# SCH_MedicalIOT_2023-03-18.net
KiCad netlist of a schematic drawn in EasyEDA
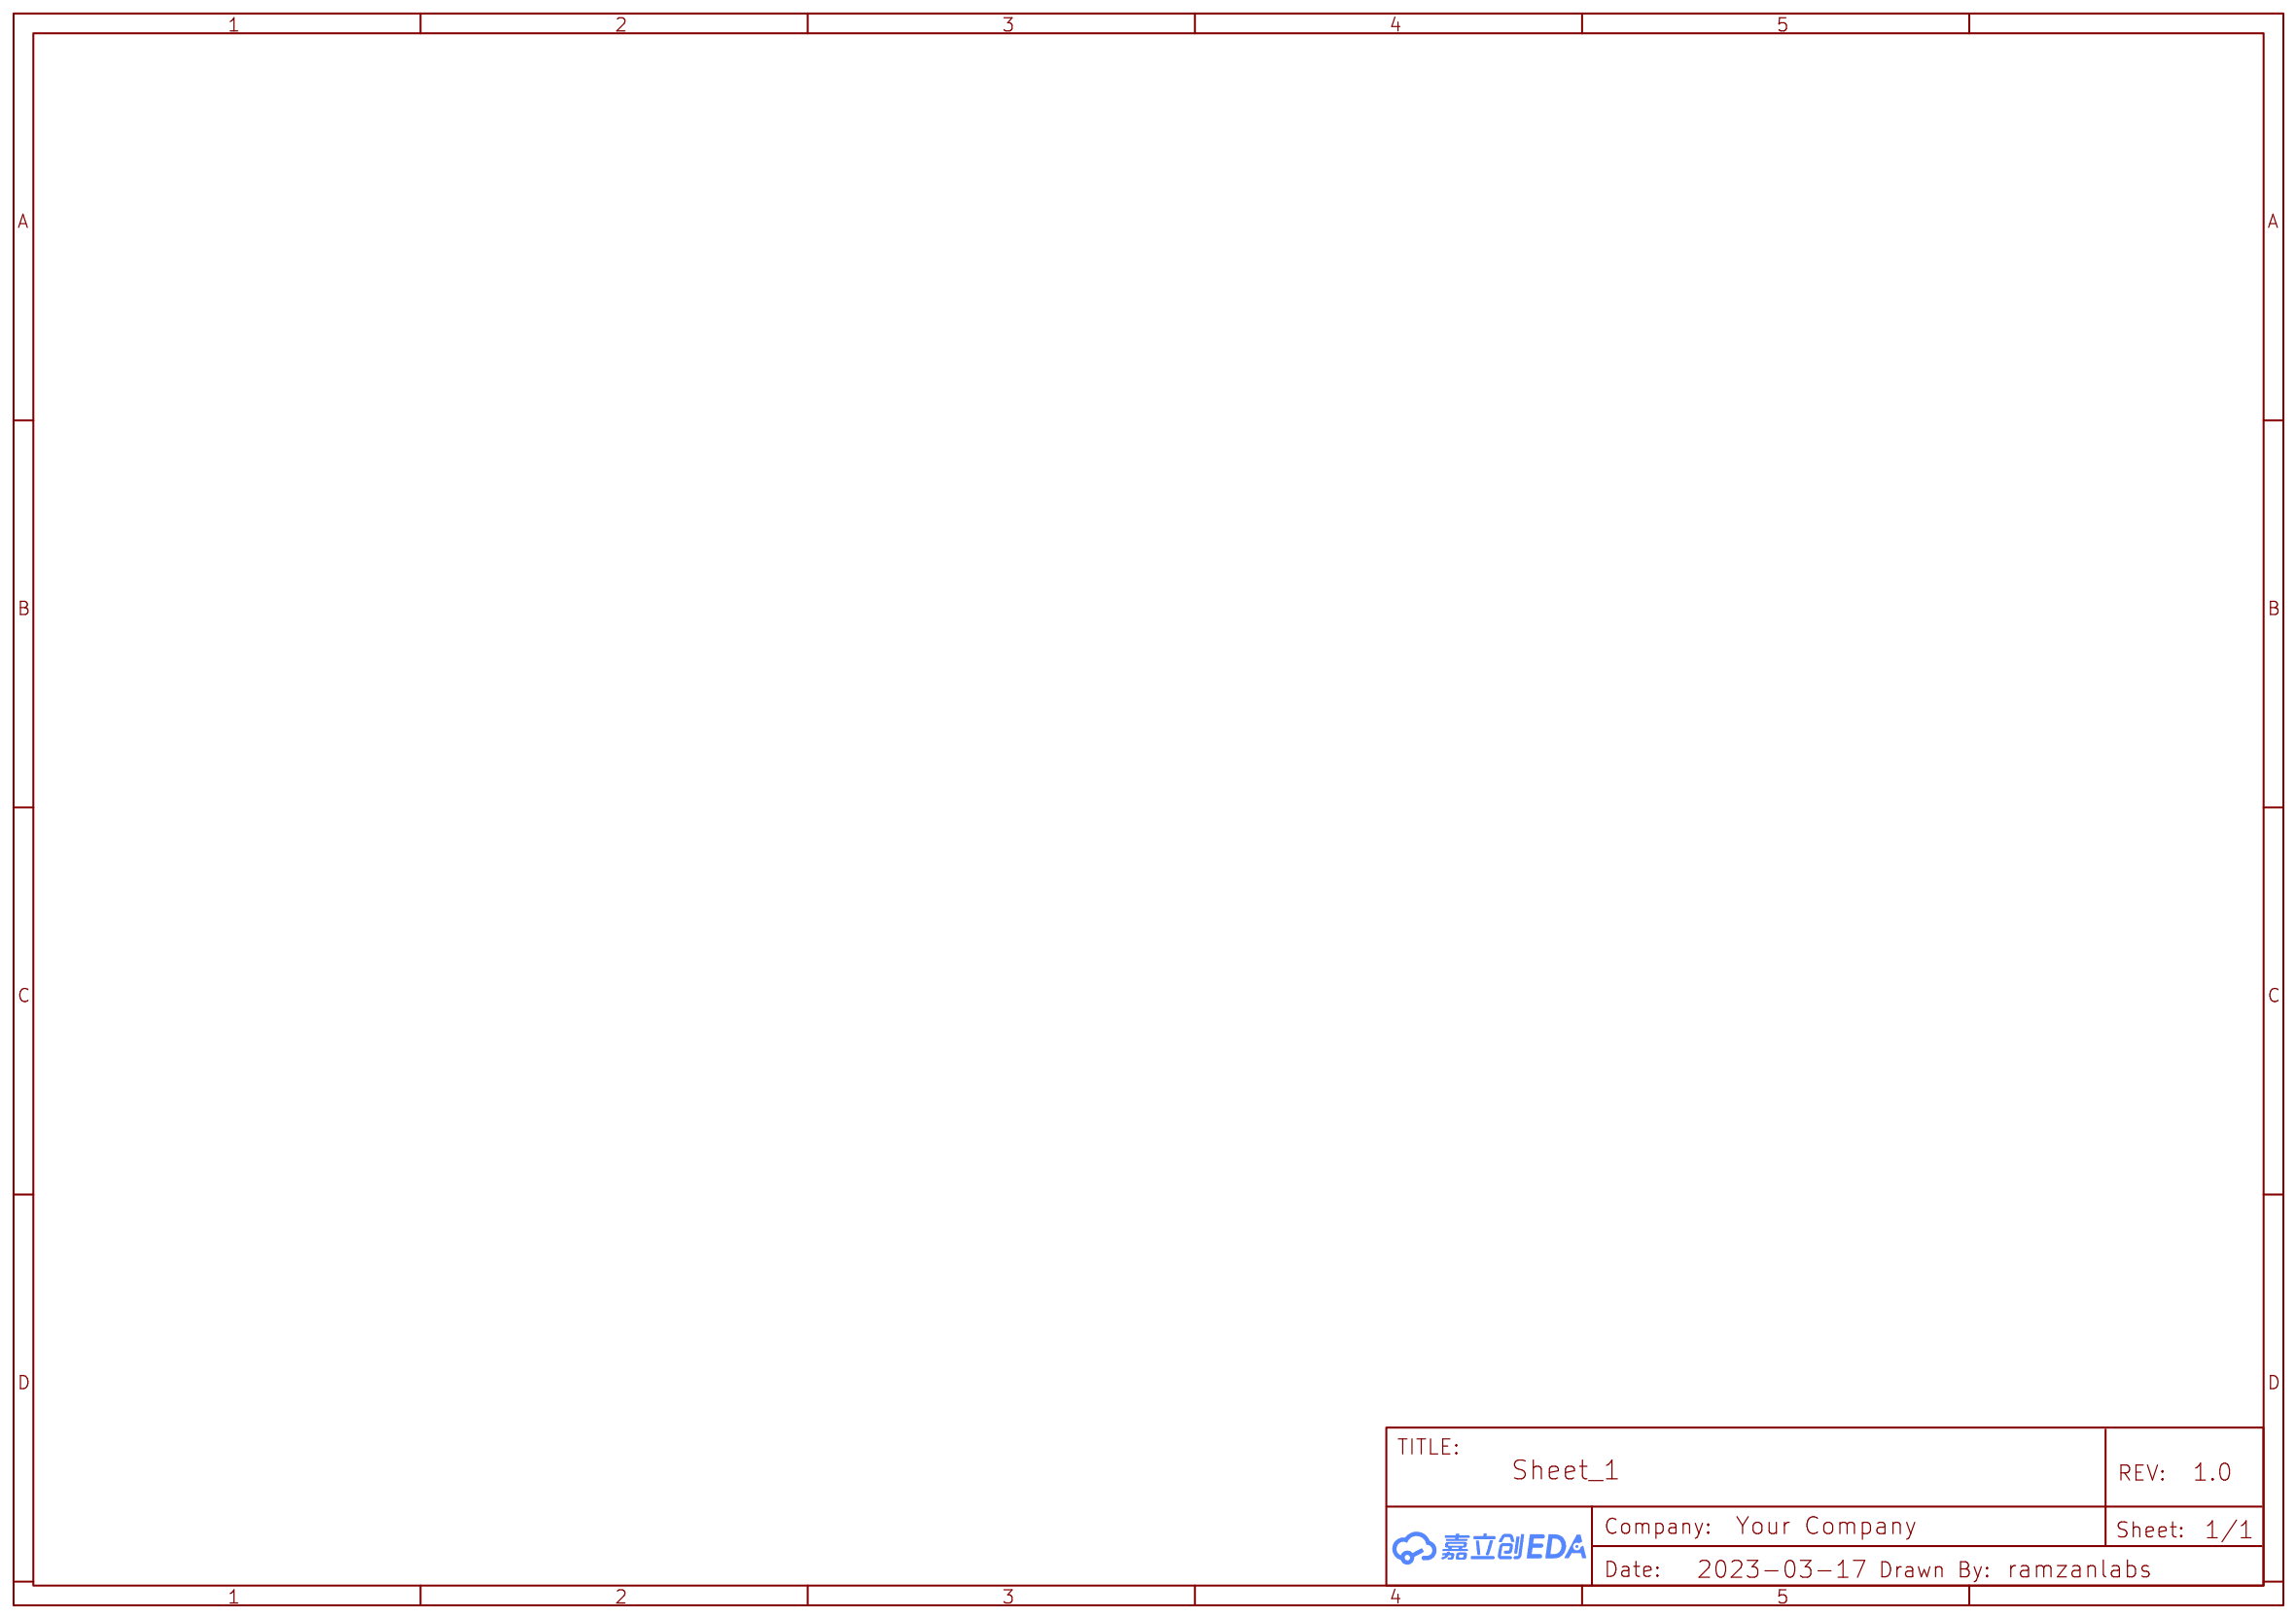
[diagram p0: Sheet_1]
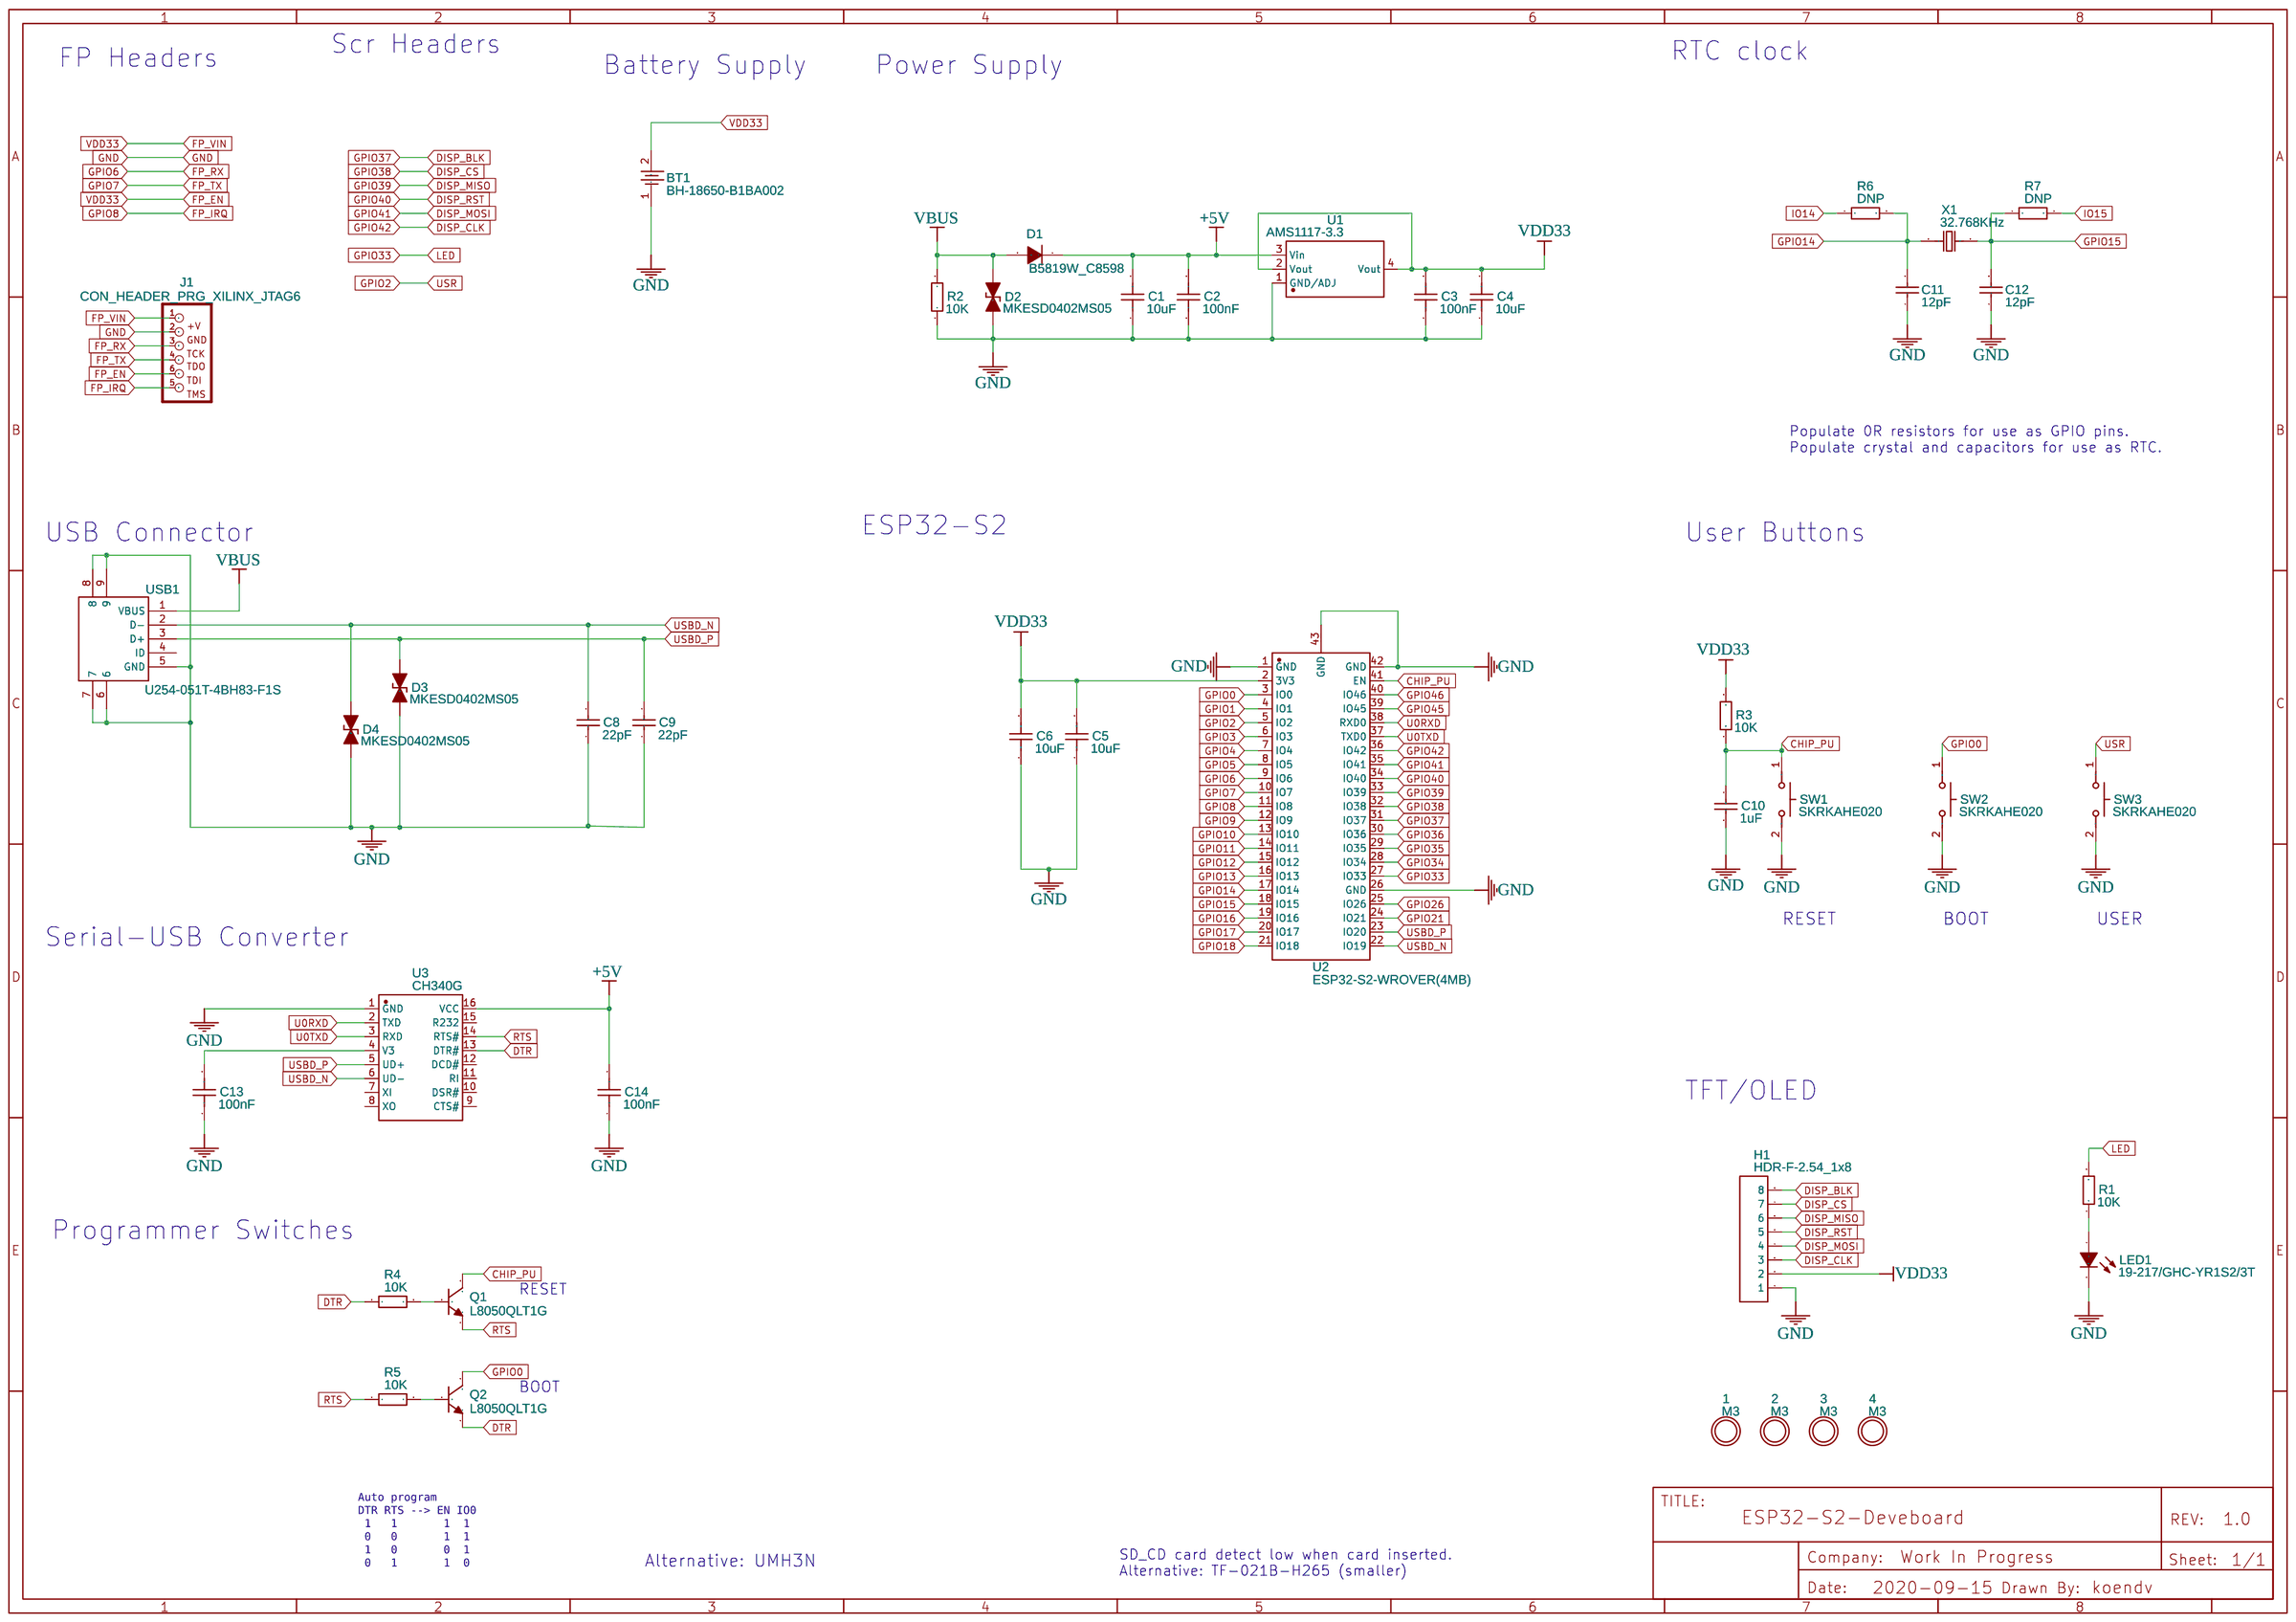
[diagram p1: Schematic]

(export (version "E")
  (design (tool "Eeschema 10.0.6"))
  (components
    (comp (ref "1") (value "M3") (libsource (lib "") (part "MOUNTINGHOLE3.0THIN")))
    (comp (ref "2") (value "M3") (libsource (lib "") (part "MOUNTINGHOLE3.0THIN")))
    (comp (ref "3") (value "M3") (libsource (lib "") (part "MOUNTINGHOLE3.0THIN")))
    (comp (ref "4") (value "M3") (libsource (lib "") (part "MOUNTINGHOLE3.0THIN")))
    (comp (ref "BT1")
      (value "BH-18650-B1BA002")
      (fields (field (name "BOM_Supplier Part") "C2988620"))
      (libsource (lib "") (part "BH-18650-B1BA002"))
    )
    (comp (ref "C1")
      (value "10uF")
      (fields
        (field (name "BOM_Manufacturer Part") "CL10A106KP8NNNC")
        (field (name "BOM_Supplier Part") "C19702")
      )
      (libsource (lib "") (part "CL10A106KP8NNNC"))
    )
    (comp (ref "C2")
      (value "100nF")
      (fields
        (field (name "BOM_Manufacturer Part") "CC0603KRX7R9BB104")
        (field (name "BOM_Supplier Part") "C14663")
      )
      (libsource (lib "") (part "CC0603KRX7R9BB104"))
    )
    (comp (ref "C3")
      (value "100nF")
      (fields
        (field (name "BOM_Manufacturer Part") "CC0603KRX7R9BB104")
        (field (name "BOM_Supplier Part") "C14663")
      )
      (libsource (lib "") (part "CC0603KRX7R9BB104"))
    )
    (comp (ref "C4")
      (value "10uF")
      (fields
        (field (name "BOM_Manufacturer Part") "CL10A106KP8NNNC")
        (field (name "BOM_Supplier Part") "C19702")
      )
      (libsource (lib "") (part "CL10A106KP8NNNC"))
    )
    (comp (ref "C5")
      (value "10uF")
      (fields
        (field (name "BOM_Manufacturer Part") "CL10A106KP8NNNC")
        (field (name "BOM_Supplier Part") "C19702")
      )
      (libsource (lib "") (part "CL10A106KP8NNNC"))
    )
    (comp (ref "C6")
      (value "10uF")
      (fields
        (field (name "BOM_Manufacturer Part") "CL10A106KP8NNNC")
        (field (name "BOM_Supplier Part") "C19702")
      )
      (libsource (lib "") (part "CL10A106KP8NNNC"))
    )
    (comp (ref "C8")
      (value "22pF")
      (fields
        (field (name "BOM_Manufacturer Part") "0402CG220J500NT")
        (field (name "BOM_Supplier Part") "C1555")
      )
      (libsource (lib "") (part "0402CG220J500NT"))
    )
    (comp (ref "C9")
      (value "22pF")
      (fields
        (field (name "BOM_Manufacturer Part") "0402CG220J500NT")
        (field (name "BOM_Supplier Part") "C1555")
      )
      (libsource (lib "") (part "0402CG220J500NT"))
    )
    (comp (ref "C10")
      (value "1uF")
      (fields
        (field (name "BOM_Manufacturer Part") "CL10A105KB8NNNC")
        (field (name "BOM_Supplier Part") "C15849")
      )
      (libsource (lib "") (part "CL10A105KB8NNNC"))
    )
    (comp (ref "C11")
      (value "12pF")
      (fields
        (field (name "BOM_Manufacturer Part") "0402CG120J500NT")
        (field (name "BOM_Supplier Part") "C1547")
      )
      (libsource (lib "") (part "0402CG120J500NT"))
    )
    (comp (ref "C12")
      (value "12pF")
      (fields
        (field (name "BOM_Manufacturer Part") "0402CG120J500NT")
        (field (name "BOM_Supplier Part") "C1547")
      )
      (libsource (lib "") (part "0402CG120J500NT"))
    )
    (comp (ref "C13")
      (value "100nF")
      (fields
        (field (name "BOM_Manufacturer Part") "CC0603KRX7R9BB104")
        (field (name "BOM_Supplier Part") "C14663")
      )
      (libsource (lib "") (part "CC0603KRX7R9BB104"))
    )
    (comp (ref "C14")
      (value "100nF")
      (fields
        (field (name "BOM_Manufacturer Part") "CC0603KRX7R9BB104")
        (field (name "BOM_Supplier Part") "C14663")
      )
      (libsource (lib "") (part "CC0603KRX7R9BB104"))
    )
    (comp (ref "D1")
      (value "B5819W_C8598")
      (fields (field (name "BOM_Manufacturer Part") "B5819W") (field (name "BOM_Supplier Part") "C8598"))
      (libsource (lib "") (part "B5819W_C8598"))
    )
    (comp (ref "D2")
      (value "MKESD0402MS05")
      (fields (field (name "BOM_Supplier Part") "C379107"))
      (libsource (lib "") (part "MKESD0402MS05"))
    )
    (comp (ref "D3")
      (value "MKESD0402MS05")
      (fields (field (name "BOM_Supplier Part") "C379107"))
      (libsource (lib "") (part "MKESD0402MS05"))
    )
    (comp (ref "D4")
      (value "MKESD0402MS05")
      (fields (field (name "BOM_Supplier Part") "C379107"))
      (libsource (lib "") (part "MKESD0402MS05"))
    )
    (comp (ref "H1")
      (value "HDR-F-2.54_1x8")
      (fields (field (name "BOM_Supplier Part") "C225505"))
      (libsource (lib "") (part "HDR-F-2.54_1x8"))
    )
    (comp (ref "J1")
      (value "CON_HEADER_PRG_XILINX_JTAG6")
      (libsource (lib "") (part "CON_HEADER_PRG_XILINX_JTAG6"))
    )
    (comp (ref "LED1")
      (value "19-217/GHC-YR1S2/3T")
      (fields (field (name "BOM_Supplier Part") "C72043"))
      (libsource (lib "") (part "19-217/GHC-YR1S2/3T"))
    )
    (comp (ref "Q1")
      (value "L8050QLT1G")
      (fields (field (name "BOM_Supplier Part") "C49581"))
      (libsource (lib "") (part "L8050QLT1G"))
    )
    (comp (ref "Q2")
      (value "L8050QLT1G")
      (fields (field (name "BOM_Supplier Part") "C49581"))
      (libsource (lib "") (part "L8050QLT1G"))
    )
    (comp (ref "R1")
      (value "10K")
      (fields
        (field (name "BOM_Manufacturer Part") "0402WGF1002TCE")
        (field (name "BOM_Supplier Part") "C25744")
      )
      (libsource (lib "") (part "0402WGF1002TCE"))
    )
    (comp (ref "R2")
      (value "10K")
      (fields
        (field (name "BOM_Manufacturer Part") "0402WGF1002TCE")
        (field (name "BOM_Supplier Part") "C25744")
      )
      (libsource (lib "") (part "0402WGF1002TCE"))
    )
    (comp (ref "R3")
      (value "10K")
      (fields
        (field (name "BOM_Manufacturer Part") "0402WGF1002TCE")
        (field (name "BOM_Supplier Part") "C25744")
      )
      (libsource (lib "") (part "0402WGF1002TCE"))
    )
    (comp (ref "R4")
      (value "10K")
      (fields
        (field (name "BOM_Manufacturer Part") "0402WGF1002TCE")
        (field (name "BOM_Supplier Part") "C25744")
      )
      (libsource (lib "") (part "0402WGF1002TCE_1"))
    )
    (comp (ref "R5")
      (value "10K")
      (fields
        (field (name "BOM_Manufacturer Part") "0402WGF1002TCE")
        (field (name "BOM_Supplier Part") "C25744")
      )
      (libsource (lib "") (part "0402WGF1002TCE_1"))
    )
    (comp (ref "R6")
      (value "DNP")
      (fields
        (field (name "BOM_Manufacturer Part") "0402WGF0000TCE")
        (field (name "BOM_Supplier Part") "C17168")
      )
      (libsource (lib "") (part "0402WGF0000TCE"))
    )
    (comp (ref "R7")
      (value "DNP")
      (fields
        (field (name "BOM_Manufacturer Part") "0402WGF0000TCE")
        (field (name "BOM_Supplier Part") "C17168")
      )
      (libsource (lib "") (part "0402WGF0000TCE"))
    )
    (comp (ref "SW1")
      (value "SKRKAHE020")
      (fields (field (name "BOM_Supplier Part") "C202388"))
      (libsource (lib "") (part "SKRKAHE020"))
    )
    (comp (ref "SW2")
      (value "SKRKAHE020")
      (fields (field (name "BOM_Supplier Part") "C202388"))
      (libsource (lib "") (part "SKRKAHE020"))
    )
    (comp (ref "SW3")
      (value "SKRKAHE020")
      (fields (field (name "BOM_Supplier Part") "C202388"))
      (libsource (lib "") (part "SKRKAHE020"))
    )
    (comp (ref "U1")
      (value "AMS1117-3.3")
      (fields (field (name "BOM_Supplier Part") "C6186"))
      (libsource (lib "") (part "AMS1117-3.3"))
    )
    (comp (ref "U2")
      (value "ESP32-S2-WROVER(4MB)")
      (fields (field (name "BOM_Supplier Part") "C701333"))
      (libsource (lib "") (part "ESP32-S2-WROVER(4MB)"))
    )
    (comp (ref "U3")
      (value "CH340G")
      (fields (field (name "BOM_Supplier Part") "C14267"))
      (libsource (lib "") (part "CH340G"))
    )
    (comp (ref "USB1")
      (value "U254-051T-4BH83-F1S")
      (fields (field (name "BOM_Supplier Part") "C397452"))
      (libsource (lib "") (part "U254-051T-4BH83-F1S"))
    )
    (comp (ref "X1")
      (value "32.768KHz")
      (fields
        (field (name "BOM_Manufacturer Part") "Q13FC1350000400")
        (field (name "BOM_Supplier Part") "C32346")
      )
      (libsource (lib "") (part "Q13FC1350000400"))
    )
  )
  (nets
    (net (code "1") (name "+5V") (class "Default")
      (node (ref "C1") (pin "2") (pinfunction "2_2") (pintype "unspecified"))
      (node (ref "C14") (pin "2") (pinfunction "2_2") (pintype "unspecified"))
      (node (ref "C2") (pin "2") (pinfunction "2_2") (pintype "unspecified"))
      (node (ref "D1") (pin "1") (pinfunction "-_1") (pintype "unspecified"))
      (node (ref "U1") (pin "3") (pinfunction "Vin_3") (pintype "unspecified"))
      (node (ref "U3") (pin "16") (pinfunction "VCC_16") (pintype "unspecified"))
    )
    (net (code "2") (name "CHIP_PU") (class "Default")
      (node (ref "C10") (pin "2") (pinfunction "2_2") (pintype "input"))
      (node (ref "Q1") (pin "3") (pinfunction "C_3") (pintype "unspecified"))
      (node (ref "R3") (pin "1") (pinfunction "1_1") (pintype "input"))
      (node (ref "SW1") (pin "1") (pinfunction "1_1") (pintype "unspecified"))
      (node (ref "U2") (pin "41") (pinfunction "EN_41") (pintype "unspecified"))
    )
    (net (code "3") (name "DISP_BLK") (class "Default")
      (node (ref "H1") (pin "8") (pinfunction "8_8") (pintype "unspecified"))
      (node (ref "U2") (pin "31") (pinfunction "IO37_31") (pintype "unspecified"))
    )
    (net (code "4") (name "DISP_CLK") (class "Default")
      (node (ref "H1") (pin "3") (pinfunction "3_3") (pintype "unspecified"))
      (node (ref "U2") (pin "36") (pinfunction "IO42_36") (pintype "unspecified"))
    )
    (net (code "5") (name "DISP_CS") (class "Default")
      (node (ref "H1") (pin "7") (pinfunction "7_7") (pintype "unspecified"))
      (node (ref "U2") (pin "32") (pinfunction "IO38_32") (pintype "unspecified"))
    )
    (net (code "6") (name "DISP_MISO") (class "Default")
      (node (ref "H1") (pin "6") (pinfunction "6_6") (pintype "unspecified"))
      (node (ref "U2") (pin "33") (pinfunction "IO39_33") (pintype "unspecified"))
    )
    (net (code "7") (name "DISP_MOSI") (class "Default")
      (node (ref "H1") (pin "4") (pinfunction "4_4") (pintype "unspecified"))
      (node (ref "U2") (pin "35") (pinfunction "IO41_35") (pintype "unspecified"))
    )
    (net (code "8") (name "DISP_RST") (class "Default")
      (node (ref "H1") (pin "5") (pinfunction "5_5") (pintype "unspecified"))
      (node (ref "U2") (pin "34") (pinfunction "IO40_34") (pintype "unspecified"))
    )
    (net (code "9") (name "DTR") (class "Default")
      (node (ref "Q2") (pin "2") (pinfunction "E_2") (pintype "unspecified"))
      (node (ref "R4") (pin "1") (pinfunction "1_1") (pintype "input"))
      (node (ref "U3") (pin "13") (pinfunction "DTR#_13") (pintype "unspecified"))
    )
    (net (code "10") (name "FP_EN") (class "Default")
      (node (ref "BT1") (pin "2") (pinfunction "2_2") (pintype "input"))
      (node (ref "C3") (pin "2") (pinfunction "2_2") (pintype "unspecified"))
      (node (ref "C4") (pin "2") (pinfunction "2_2") (pintype "unspecified"))
      (node (ref "C5") (pin "2") (pinfunction "2_2") (pintype "unspecified"))
      (node (ref "C6") (pin "2") (pinfunction "2_2") (pintype "unspecified"))
      (node (ref "H1") (pin "2") (pinfunction "2_2") (pintype "unspecified"))
      (node (ref "J1") (pin "1") (pinfunction "+V_1") (pintype "unspecified"))
      (node (ref "J1") (pin "6") (pinfunction "TDI_6") (pintype "unspecified"))
      (node (ref "R3") (pin "2") (pinfunction "2_2") (pintype "input"))
      (node (ref "U1") (pin "2") (pinfunction "Vout_2") (pintype "unspecified"))
      (node (ref "U1") (pin "4") (pinfunction "Vout_4") (pintype "unspecified"))
      (node (ref "U2") (pin "2") (pinfunction "3V3_2") (pintype "unspecified"))
    )
    (net (code "11") (name "FP_IRQ") (class "Default")
      (node (ref "J1") (pin "5") (pinfunction "TMS_5") (pintype "unspecified"))
      (node (ref "U2") (pin "11") (pinfunction "IO8_11") (pintype "unspecified"))
    )
    (net (code "12") (name "FP_RX") (class "Default")
      (node (ref "J1") (pin "3") (pinfunction "TCK_3") (pintype "unspecified"))
      (node (ref "U2") (pin "9") (pinfunction "IO6_9") (pintype "unspecified"))
    )
    (net (code "13") (name "FP_TX") (class "Default")
      (node (ref "J1") (pin "4") (pinfunction "TDO_4") (pintype "unspecified"))
      (node (ref "U2") (pin "10") (pinfunction "IO7_10") (pintype "unspecified"))
    )
    (net (code "14") (name "GND") (class "Default")
      (node (ref "BT1") (pin "1") (pinfunction "1_1") (pintype "input"))
      (node (ref "C1") (pin "1") (pinfunction "1_1") (pintype "unspecified"))
      (node (ref "C10") (pin "1") (pinfunction "1_1") (pintype "input"))
      (node (ref "C11") (pin "1") (pinfunction "1_1") (pintype "input"))
      (node (ref "C12") (pin "1") (pinfunction "1_1") (pintype "input"))
      (node (ref "C13") (pin "1") (pinfunction "1_1") (pintype "unspecified"))
      (node (ref "C14") (pin "1") (pinfunction "1_1") (pintype "unspecified"))
      (node (ref "C2") (pin "1") (pinfunction "1_1") (pintype "unspecified"))
      (node (ref "C3") (pin "1") (pinfunction "1_1") (pintype "unspecified"))
      (node (ref "C4") (pin "1") (pinfunction "1_1") (pintype "unspecified"))
      (node (ref "C5") (pin "1") (pinfunction "1_1") (pintype "unspecified"))
      (node (ref "C6") (pin "1") (pinfunction "1_1") (pintype "unspecified"))
      (node (ref "C8") (pin "1") (pinfunction "1_1") (pintype "input"))
      (node (ref "C9") (pin "1") (pinfunction "1_1") (pintype "input"))
      (node (ref "D2") (pin "1") (pinfunction "1_1") (pintype "unspecified"))
      (node (ref "D3") (pin "1") (pinfunction "1_1") (pintype "unspecified"))
      (node (ref "D4") (pin "1") (pinfunction "1_1") (pintype "unspecified"))
      (node (ref "H1") (pin "1") (pinfunction "1_1") (pintype "unspecified"))
      (node (ref "J1") (pin "2") (pinfunction "GND_2") (pintype "unspecified"))
      (node (ref "LED1") (pin "2") (pinfunction "C_2") (pintype "input"))
      (node (ref "R2") (pin "1") (pinfunction "1_1") (pintype "input"))
      (node (ref "SW1") (pin "2") (pinfunction "2_2") (pintype "unspecified"))
      (node (ref "SW2") (pin "2") (pinfunction "2_2") (pintype "unspecified"))
      (node (ref "SW3") (pin "2") (pinfunction "2_2") (pintype "unspecified"))
      (node (ref "U1") (pin "1") (pinfunction "GND/ADJ_1") (pintype "unspecified"))
      (node (ref "U2") (pin "1") (pinfunction "GND_1") (pintype "unspecified"))
      (node (ref "U2") (pin "26") (pinfunction "GND_26") (pintype "unspecified"))
      (node (ref "U2") (pin "42") (pinfunction "GND_42") (pintype "unspecified"))
      (node (ref "U2") (pin "43") (pinfunction "GND_43") (pintype "unspecified"))
      (node (ref "U3") (pin "1") (pinfunction "GND_1") (pintype "unspecified"))
      (node (ref "USB1") (pin "5") (pinfunction "GND_5") (pintype "unspecified"))
      (node (ref "USB1") (pin "6") (pinfunction "6_6") (pintype "unspecified"))
      (node (ref "USB1") (pin "7") (pinfunction "7_7") (pintype "unspecified"))
      (node (ref "USB1") (pin "8") (pinfunction "8_8") (pintype "unspecified"))
      (node (ref "USB1") (pin "9") (pinfunction "9_9") (pintype "unspecified"))
    )
    (net (code "15") (name "GPIO0") (class "Default")
      (node (ref "Q2") (pin "3") (pinfunction "C_3") (pintype "unspecified"))
      (node (ref "SW2") (pin "1") (pinfunction "1_1") (pintype "unspecified"))
      (node (ref "U2") (pin "3") (pinfunction "IO0_3") (pintype "unspecified"))
    )
    (net (code "16") (name "GPIO1") (class "Default")
      (node (ref "U2") (pin "4") (pinfunction "IO1_4") (pintype "unspecified"))
    )
    (net (code "17") (name "GPIO2") (class "Default")
      (node (ref "SW3") (pin "1") (pinfunction "1_1") (pintype "unspecified"))
      (node (ref "U2") (pin "5") (pinfunction "IO2_5") (pintype "unspecified"))
    )
    (net (code "18") (name "GPIO3") (class "Default")
      (node (ref "U2") (pin "6") (pinfunction "IO3_6") (pintype "unspecified"))
    )
    (net (code "19") (name "GPIO4") (class "Default")
      (node (ref "U2") (pin "7") (pinfunction "IO4_7") (pintype "unspecified"))
    )
    (net (code "20") (name "GPIO5") (class "Default")
      (node (ref "U2") (pin "8") (pinfunction "IO5_8") (pintype "unspecified"))
    )
    (net (code "21") (name "GPIO9") (class "Default")
      (node (ref "U2") (pin "12") (pinfunction "IO9_12") (pintype "unspecified"))
    )
    (net (code "22") (name "GPIO10") (class "Default")
      (node (ref "U2") (pin "13") (pinfunction "IO10_13") (pintype "unspecified"))
    )
    (net (code "23") (name "GPIO11") (class "Default")
      (node (ref "U2") (pin "14") (pinfunction "IO11_14") (pintype "unspecified"))
    )
    (net (code "24") (name "GPIO12") (class "Default")
      (node (ref "U2") (pin "15") (pinfunction "IO12_15") (pintype "unspecified"))
    )
    (net (code "25") (name "GPIO13") (class "Default")
      (node (ref "U2") (pin "16") (pinfunction "IO13_16") (pintype "unspecified"))
    )
    (net (code "26") (name "GPIO14") (class "Default")
      (node (ref "C11") (pin "2") (pinfunction "2_2") (pintype "input"))
      (node (ref "R6") (pin "2") (pinfunction "2_2") (pintype "input"))
      (node (ref "U2") (pin "17") (pinfunction "IO14_17") (pintype "unspecified"))
      (node (ref "X1") (pin "1") (pinfunction "1_1") (pintype "unspecified"))
    )
    (net (code "27") (name "GPIO15") (class "Default")
      (node (ref "C12") (pin "2") (pinfunction "2_2") (pintype "input"))
      (node (ref "R7") (pin "1") (pinfunction "1_1") (pintype "input"))
      (node (ref "U2") (pin "18") (pinfunction "IO15_18") (pintype "unspecified"))
      (node (ref "X1") (pin "2") (pinfunction "2_2") (pintype "unspecified"))
    )
    (net (code "28") (name "GPIO16") (class "Default")
      (node (ref "U2") (pin "19") (pinfunction "IO16_19") (pintype "unspecified"))
    )
    (net (code "29") (name "GPIO17") (class "Default")
      (node (ref "U2") (pin "20") (pinfunction "IO17_20") (pintype "unspecified"))
    )
    (net (code "30") (name "GPIO18") (class "Default")
      (node (ref "U2") (pin "21") (pinfunction "IO18_21") (pintype "unspecified"))
    )
    (net (code "31") (name "GPIO21") (class "Default")
      (node (ref "U2") (pin "24") (pinfunction "IO21_24") (pintype "unspecified"))
    )
    (net (code "32") (name "GPIO26") (class "Default")
      (node (ref "U2") (pin "25") (pinfunction "IO26_25") (pintype "unspecified"))
    )
    (net (code "33") (name "GPIO33") (class "Default")
      (node (ref "R1") (pin "2") (pinfunction "2_2") (pintype "input"))
      (node (ref "U2") (pin "27") (pinfunction "IO33_27") (pintype "unspecified"))
    )
    (net (code "34") (name "GPIO34") (class "Default")
      (node (ref "U2") (pin "28") (pinfunction "IO34_28") (pintype "unspecified"))
    )
    (net (code "35") (name "GPIO35") (class "Default")
      (node (ref "U2") (pin "29") (pinfunction "IO35_29") (pintype "unspecified"))
    )
    (net (code "36") (name "GPIO36") (class "Default")
      (node (ref "U2") (pin "30") (pinfunction "IO36_30") (pintype "unspecified"))
    )
    (net (code "37") (name "GPIO45") (class "Default")
      (node (ref "U2") (pin "39") (pinfunction "IO45_39") (pintype "unspecified"))
    )
    (net (code "38") (name "GPIO46") (class "Default")
      (node (ref "U2") (pin "40") (pinfunction "IO46_40") (pintype "unspecified"))
    )
    (net (code "39") (name "IO14") (class "Default")
      (node (ref "R6") (pin "1") (pinfunction "1_1") (pintype "input"))
    )
    (net (code "40") (name "IO15") (class "Default")
      (node (ref "R7") (pin "2") (pinfunction "2_2") (pintype "input"))
    )
    (net (code "41") (name "Net-(LED1-A)") (class "Default")
      (node (ref "LED1") (pin "1") (pinfunction "A_1") (pintype "input"))
      (node (ref "R1") (pin "1") (pinfunction "1_1") (pintype "input"))
    )
    (net (code "42") (name "Net-(Q1-B)") (class "Default")
      (node (ref "Q1") (pin "1") (pinfunction "B_1") (pintype "unspecified"))
      (node (ref "R4") (pin "2") (pinfunction "2_2") (pintype "input"))
    )
    (net (code "43") (name "Net-(Q2-B)") (class "Default")
      (node (ref "Q2") (pin "1") (pinfunction "B_1") (pintype "unspecified"))
      (node (ref "R5") (pin "2") (pinfunction "2_2") (pintype "input"))
    )
    (net (code "44") (name "Net-(U3-V3)") (class "Default")
      (node (ref "C13") (pin "2") (pinfunction "2_2") (pintype "unspecified"))
      (node (ref "U3") (pin "4") (pinfunction "V3_4") (pintype "unspecified"))
    )
    (net (code "45") (name "RTS") (class "Default")
      (node (ref "Q1") (pin "2") (pinfunction "E_2") (pintype "unspecified"))
      (node (ref "R5") (pin "1") (pinfunction "1_1") (pintype "input"))
      (node (ref "U3") (pin "14") (pinfunction "RTS#_14") (pintype "unspecified"))
    )
    (net (code "46") (name "U0RXD") (class "Default")
      (node (ref "U2") (pin "38") (pinfunction "RXD0_38") (pintype "unspecified"))
      (node (ref "U3") (pin "2") (pinfunction "TXD_2") (pintype "unspecified"))
    )
    (net (code "47") (name "U0TXD") (class "Default")
      (node (ref "U2") (pin "37") (pinfunction "TXD0_37") (pintype "unspecified"))
      (node (ref "U3") (pin "3") (pinfunction "RXD_3") (pintype "unspecified"))
    )
    (net (code "48") (name "USBD_N") (class "Default")
      (node (ref "C8") (pin "2") (pinfunction "2_2") (pintype "input"))
      (node (ref "D4") (pin "2") (pinfunction "2_2") (pintype "unspecified"))
      (node (ref "U2") (pin "22") (pinfunction "IO19_22") (pintype "unspecified"))
      (node (ref "U3") (pin "6") (pinfunction "UD-_6") (pintype "unspecified"))
      (node (ref "USB1") (pin "2") (pinfunction "D-_2") (pintype "unspecified"))
    )
    (net (code "49") (name "USBD_P") (class "Default")
      (node (ref "C9") (pin "2") (pinfunction "2_2") (pintype "input"))
      (node (ref "D3") (pin "2") (pinfunction "2_2") (pintype "unspecified"))
      (node (ref "U2") (pin "23") (pinfunction "IO20_23") (pintype "unspecified"))
      (node (ref "U3") (pin "5") (pinfunction "UD+_5") (pintype "unspecified"))
      (node (ref "USB1") (pin "3") (pinfunction "D+_3") (pintype "unspecified"))
    )
    (net (code "50") (name "VBUS") (class "Default")
      (node (ref "D1") (pin "2") (pinfunction "+_2") (pintype "unspecified"))
      (node (ref "D2") (pin "2") (pinfunction "2_2") (pintype "unspecified"))
      (node (ref "R2") (pin "2") (pinfunction "2_2") (pintype "input"))
      (node (ref "USB1") (pin "1") (pinfunction "VBUS_1") (pintype "unspecified"))
    )
    (net (code "51") (name "unconnected-(U3-CTS#-Pad9)") (class "Default")
      (node (ref "U3") (pin "9") (pinfunction "CTS#_9") (pintype "unspecified"))
    )
    (net (code "52") (name "unconnected-(U3-DCD#-Pad12)") (class "Default")
      (node (ref "U3") (pin "12") (pinfunction "DCD#_12") (pintype "unspecified"))
    )
    (net (code "53") (name "unconnected-(U3-DSR#-Pad10)") (class "Default")
      (node (ref "U3") (pin "10") (pinfunction "DSR#_10") (pintype "unspecified"))
    )
    (net (code "54") (name "unconnected-(U3-R232-Pad15)") (class "Default")
      (node (ref "U3") (pin "15") (pinfunction "R232_15") (pintype "unspecified"))
    )
    (net (code "55") (name "unconnected-(U3-RI-Pad11)") (class "Default")
      (node (ref "U3") (pin "11") (pinfunction "RI_11") (pintype "unspecified"))
    )
    (net (code "56") (name "unconnected-(U3-XI-Pad7)") (class "Default")
      (node (ref "U3") (pin "7") (pinfunction "XI_7") (pintype "unspecified"))
    )
    (net (code "57") (name "unconnected-(U3-XO-Pad8)") (class "Default")
      (node (ref "U3") (pin "8") (pinfunction "XO_8") (pintype "unspecified"))
    )
    (net (code "58") (name "unconnected-(USB1-ID-Pad4)") (class "Default")
      (node (ref "USB1") (pin "4") (pinfunction "ID_4") (pintype "unspecified"))
    )
  )
)
